# ping_imu_nano_v1.net
KiCad netlist of a schematic drawn in EAGLE
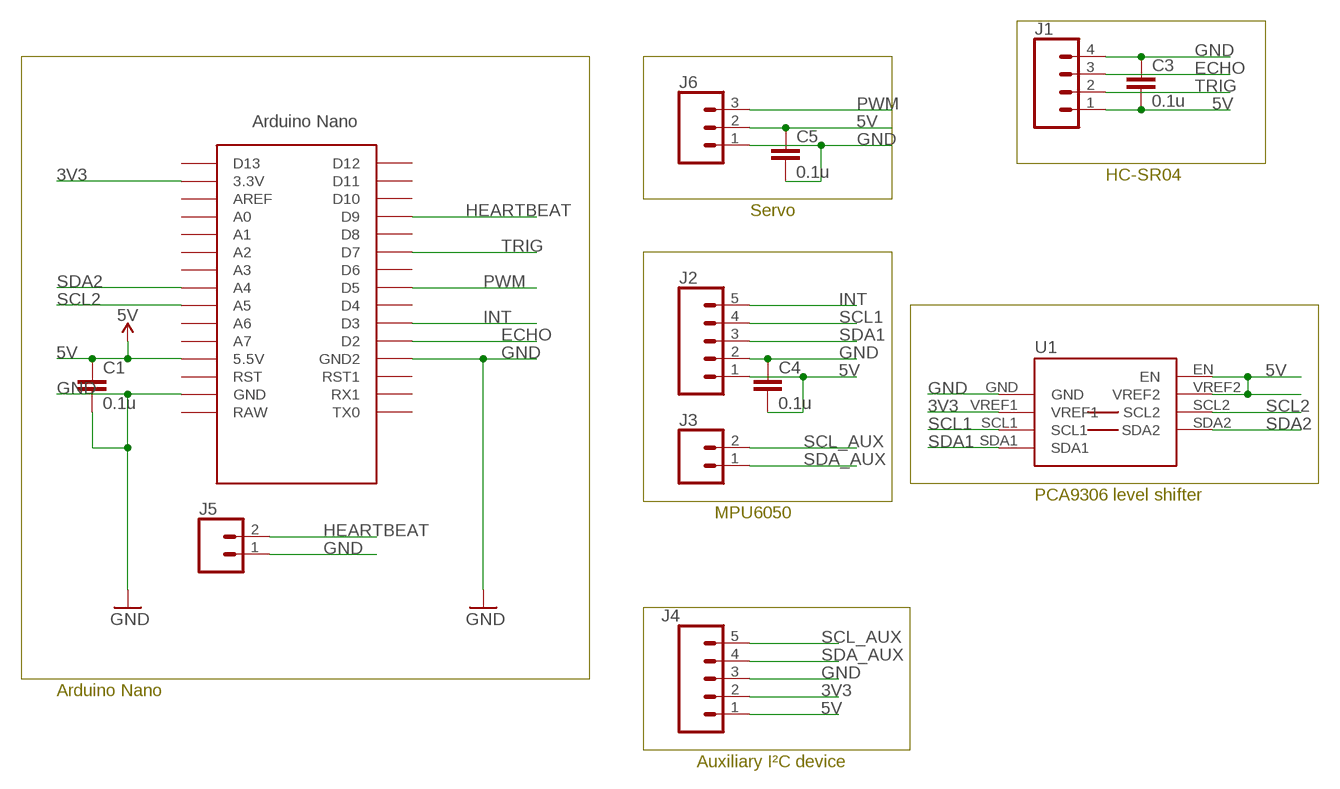
[diagram p0: schematic, sheet 1]

(export (version "E")
  (design (tool "Eeschema 10.0.6"))
  (components
    (comp (ref "C1")
      (value "0.1u")
      (footprint "eagle-import:C1206")
      (libsource (lib "eagle-import") (part "C-EUC1206"))
    )
    (comp (ref "C3")
      (value "0.1u")
      (footprint "eagle-import:C1206")
      (libsource (lib "eagle-import") (part "C-EUC1206"))
    )
    (comp (ref "C4")
      (value "0.1u")
      (footprint "eagle-import:C1206")
      (libsource (lib "eagle-import") (part "C-EUC1206"))
    )
    (comp (ref "C5")
      (value "0.1u")
      (footprint "eagle-import:C1206")
      (libsource (lib "eagle-import") (part "C-EUC1206"))
    )
    (comp (ref "J1")
      (value "CONN_04LONGPADS")
      (footprint "eagle-import:1X04_LONGPADS")
      (libsource (lib "eagle-import") (part "CONN_04LONGPADS"))
    )
    (comp (ref "J2")
      (value "CONN_05PTH_LONGPADS")
      (footprint "eagle-import:1X05_LONGPADS")
      (libsource (lib "eagle-import") (part "CONN_05PTH_LONGPADS"))
    )
    (comp (ref "J3")
      (value "CONN_02PTH3")
      (footprint "eagle-import:1X02_LONGPADS")
      (libsource (lib "eagle-import") (part "CONN_02PTH3"))
    )
    (comp (ref "J4")
      (value "CONN_05PTH_LONGPADS")
      (footprint "eagle-import:1X05_LONGPADS")
      (libsource (lib "eagle-import") (part "CONN_05PTH_LONGPADS"))
    )
    (comp (ref "J5")
      (value "CONN_02PTH3")
      (footprint "eagle-import:1X02_LONGPADS")
      (libsource (lib "eagle-import") (part "CONN_02PTH3"))
    )
    (comp (ref "J6")
      (value "CONN_03LONGPADS")
      (footprint "eagle-import:1X03_LONGPADS")
      (libsource (lib "eagle-import") (part "CONN_03LONGPADS"))
    )
    (comp (ref "U$1")
      (value "NANO_BARE")
      (footprint "eagle-import:NANO_BARE")
      (libsource (lib "eagle-import") (part "NANO_BARE"))
    )
    (comp (ref "U1")
      (value "PCA9306SO8")
      (footprint "eagle-import:SO8")
      (libsource (lib "eagle-import") (part "PCA9306SO8"))
    )
  )
  (nets
    (net (code "1") (name "/3V3") (class "Default")
      (node (ref "J4") (pin "2") (pinfunction "2_2") (pintype "passive"))
      (node (ref "U$1") (pin "3.3V") (pinfunction "3.3V_3.3V") (pintype "bidirectional"))
      (node (ref "U1") (pin "VREF1") (pinfunction "VREF1_VREF1") (pintype "bidirectional"))
    )
    (net (code "2") (name "/ECHO") (class "Default")
      (node (ref "J1") (pin "3") (pinfunction "3_3") (pintype "passive"))
      (node (ref "U$1") (pin "D2") (pinfunction "D2_D2") (pintype "bidirectional"))
    )
    (net (code "3") (name "/HEARTBEAT") (class "Default")
      (node (ref "J5") (pin "2") (pinfunction "2_2") (pintype "passive"))
      (node (ref "U$1") (pin "D9") (pinfunction "D9_D9") (pintype "bidirectional"))
    )
    (net (code "4") (name "/INT") (class "Default")
      (node (ref "J2") (pin "5") (pinfunction "5_5") (pintype "passive"))
      (node (ref "U$1") (pin "D3") (pinfunction "D3_D3") (pintype "bidirectional"))
    )
    (net (code "5") (name "/PWM") (class "Default")
      (node (ref "J6") (pin "3") (pinfunction "3_3") (pintype "passive"))
      (node (ref "U$1") (pin "D5") (pinfunction "D5_D5") (pintype "bidirectional"))
    )
    (net (code "6") (name "/SCL1") (class "Default")
      (node (ref "J2") (pin "4") (pinfunction "4_4") (pintype "passive"))
      (node (ref "U1") (pin "SCL1") (pinfunction "SCL1_SCL1") (pintype "bidirectional"))
    )
    (net (code "7") (name "/SCL2") (class "Default")
      (node (ref "U$1") (pin "A5") (pinfunction "A5_A5") (pintype "bidirectional"))
      (node (ref "U1") (pin "SCL2") (pinfunction "SCL2_SCL2") (pintype "bidirectional"))
    )
    (net (code "8") (name "/SCL_AUX") (class "Default")
      (node (ref "J3") (pin "2") (pinfunction "2_2") (pintype "passive"))
      (node (ref "J4") (pin "5") (pinfunction "5_5") (pintype "passive"))
    )
    (net (code "9") (name "/SDA1") (class "Default")
      (node (ref "J2") (pin "3") (pinfunction "3_3") (pintype "passive"))
      (node (ref "U1") (pin "SDA1") (pinfunction "SDA1_SDA1") (pintype "bidirectional"))
    )
    (net (code "10") (name "/SDA2") (class "Default")
      (node (ref "U$1") (pin "A4") (pinfunction "A4_A4") (pintype "bidirectional"))
      (node (ref "U1") (pin "SDA2") (pinfunction "SDA2_SDA2") (pintype "bidirectional"))
    )
    (net (code "11") (name "/SDA_AUX") (class "Default")
      (node (ref "J3") (pin "1") (pinfunction "1_1") (pintype "passive"))
      (node (ref "J4") (pin "4") (pinfunction "4_4") (pintype "passive"))
    )
    (net (code "12") (name "/TRIG") (class "Default")
      (node (ref "J1") (pin "2") (pinfunction "2_2") (pintype "passive"))
      (node (ref "U$1") (pin "D7") (pinfunction "D7_D7") (pintype "bidirectional"))
    )
    (net (code "13") (name "5V") (class "Default")
      (node (ref "C1") (pin "1") (pinfunction "1_1") (pintype "passive"))
      (node (ref "C3") (pin "2") (pinfunction "2_2") (pintype "passive"))
      (node (ref "C4") (pin "2") (pinfunction "2_2") (pintype "passive"))
      (node (ref "C5") (pin "1") (pinfunction "1_1") (pintype "passive"))
      (node (ref "J1") (pin "1") (pinfunction "1_1") (pintype "passive"))
      (node (ref "J2") (pin "1") (pinfunction "1_1") (pintype "passive"))
      (node (ref "J4") (pin "1") (pinfunction "1_1") (pintype "passive"))
      (node (ref "J6") (pin "2") (pinfunction "2_2") (pintype "passive"))
      (node (ref "U$1") (pin "5V") (pinfunction "5.5V_5V") (pintype "bidirectional"))
      (node (ref "U1") (pin "EN") (pinfunction "EN_EN") (pintype "bidirectional"))
      (node (ref "U1") (pin "VREF2") (pinfunction "VREF2_VREF2") (pintype "bidirectional"))
    )
    (net (code "14") (name "GND") (class "Default")
      (node (ref "C1") (pin "2") (pinfunction "2_2") (pintype "passive"))
      (node (ref "C3") (pin "1") (pinfunction "1_1") (pintype "passive"))
      (node (ref "C4") (pin "1") (pinfunction "1_1") (pintype "passive"))
      (node (ref "C5") (pin "2") (pinfunction "2_2") (pintype "passive"))
      (node (ref "J1") (pin "4") (pinfunction "4_4") (pintype "passive"))
      (node (ref "J2") (pin "2") (pinfunction "2_2") (pintype "passive"))
      (node (ref "J4") (pin "3") (pinfunction "3_3") (pintype "passive"))
      (node (ref "J5") (pin "1") (pinfunction "1_1") (pintype "passive"))
      (node (ref "J6") (pin "1") (pinfunction "1_1") (pintype "passive"))
      (node (ref "U$1") (pin "GND") (pinfunction "GND_GND") (pintype "bidirectional"))
      (node (ref "U$1") (pin "GND1") (pinfunction "GND2_GND1") (pintype "bidirectional"))
      (node (ref "U1") (pin "GND") (pinfunction "GND_GND") (pintype "bidirectional"))
    )
    (net (code "15") (name "unconnected-(U$1-PadA0)") (class "Default")
      (node (ref "U$1") (pin "A0") (pinfunction "A0_A0") (pintype "bidirectional"))
    )
    (net (code "16") (name "unconnected-(U$1-PadA1)") (class "Default")
      (node (ref "U$1") (pin "A1") (pinfunction "A1_A1") (pintype "bidirectional"))
    )
    (net (code "17") (name "unconnected-(U$1-PadA2)") (class "Default")
      (node (ref "U$1") (pin "A2") (pinfunction "A2_A2") (pintype "bidirectional"))
    )
    (net (code "18") (name "unconnected-(U$1-PadA3)") (class "Default")
      (node (ref "U$1") (pin "A3") (pinfunction "A3_A3") (pintype "bidirectional"))
    )
    (net (code "19") (name "unconnected-(U$1-PadA6)") (class "Default")
      (node (ref "U$1") (pin "A6") (pinfunction "A6_A6") (pintype "bidirectional"))
    )
    (net (code "20") (name "unconnected-(U$1-PadA7)") (class "Default")
      (node (ref "U$1") (pin "A7") (pinfunction "A7_A7") (pintype "bidirectional"))
    )
    (net (code "21") (name "unconnected-(U$1-PadAREF)") (class "Default")
      (node (ref "U$1") (pin "AREF") (pinfunction "AREF_AREF") (pintype "bidirectional"))
    )
    (net (code "22") (name "unconnected-(U$1-PadD4)") (class "Default")
      (node (ref "U$1") (pin "D4") (pinfunction "D4_D4") (pintype "bidirectional"))
    )
    (net (code "23") (name "unconnected-(U$1-PadD6)") (class "Default")
      (node (ref "U$1") (pin "D6") (pinfunction "D6_D6") (pintype "bidirectional"))
    )
    (net (code "24") (name "unconnected-(U$1-PadD8)") (class "Default")
      (node (ref "U$1") (pin "D8") (pinfunction "D8_D8") (pintype "bidirectional"))
    )
    (net (code "25") (name "unconnected-(U$1-PadD10)") (class "Default")
      (node (ref "U$1") (pin "D10") (pinfunction "D10_D10") (pintype "bidirectional"))
    )
    (net (code "26") (name "unconnected-(U$1-PadD11)") (class "Default")
      (node (ref "U$1") (pin "D11") (pinfunction "D11_D11") (pintype "bidirectional"))
    )
    (net (code "27") (name "unconnected-(U$1-PadD12)") (class "Default")
      (node (ref "U$1") (pin "D12") (pinfunction "D12_D12") (pintype "bidirectional"))
    )
    (net (code "28") (name "unconnected-(U$1-PadD13)") (class "Default")
      (node (ref "U$1") (pin "D13") (pinfunction "D13_D13") (pintype "bidirectional"))
    )
    (net (code "29") (name "unconnected-(U$1-PadRAW)") (class "Default")
      (node (ref "U$1") (pin "RAW") (pinfunction "RAW_RAW") (pintype "bidirectional"))
    )
    (net (code "30") (name "unconnected-(U$1-PadRST)") (class "Default")
      (node (ref "U$1") (pin "RST") (pinfunction "RST_RST") (pintype "bidirectional"))
    )
    (net (code "31") (name "unconnected-(U$1-PadRST1)") (class "Default")
      (node (ref "U$1") (pin "RST1") (pinfunction "RST1_RST1") (pintype "bidirectional"))
    )
    (net (code "32") (name "unconnected-(U$1-PadRX1)") (class "Default")
      (node (ref "U$1") (pin "RX1") (pinfunction "RX1_RX1") (pintype "bidirectional"))
    )
    (net (code "33") (name "unconnected-(U$1-PadTX0)") (class "Default")
      (node (ref "U$1") (pin "TX0") (pinfunction "TX0_TX0") (pintype "bidirectional"))
    )
  )
)
